# Analog_Power.net
KiCad netlist of a schematic drawn in Altium Designer
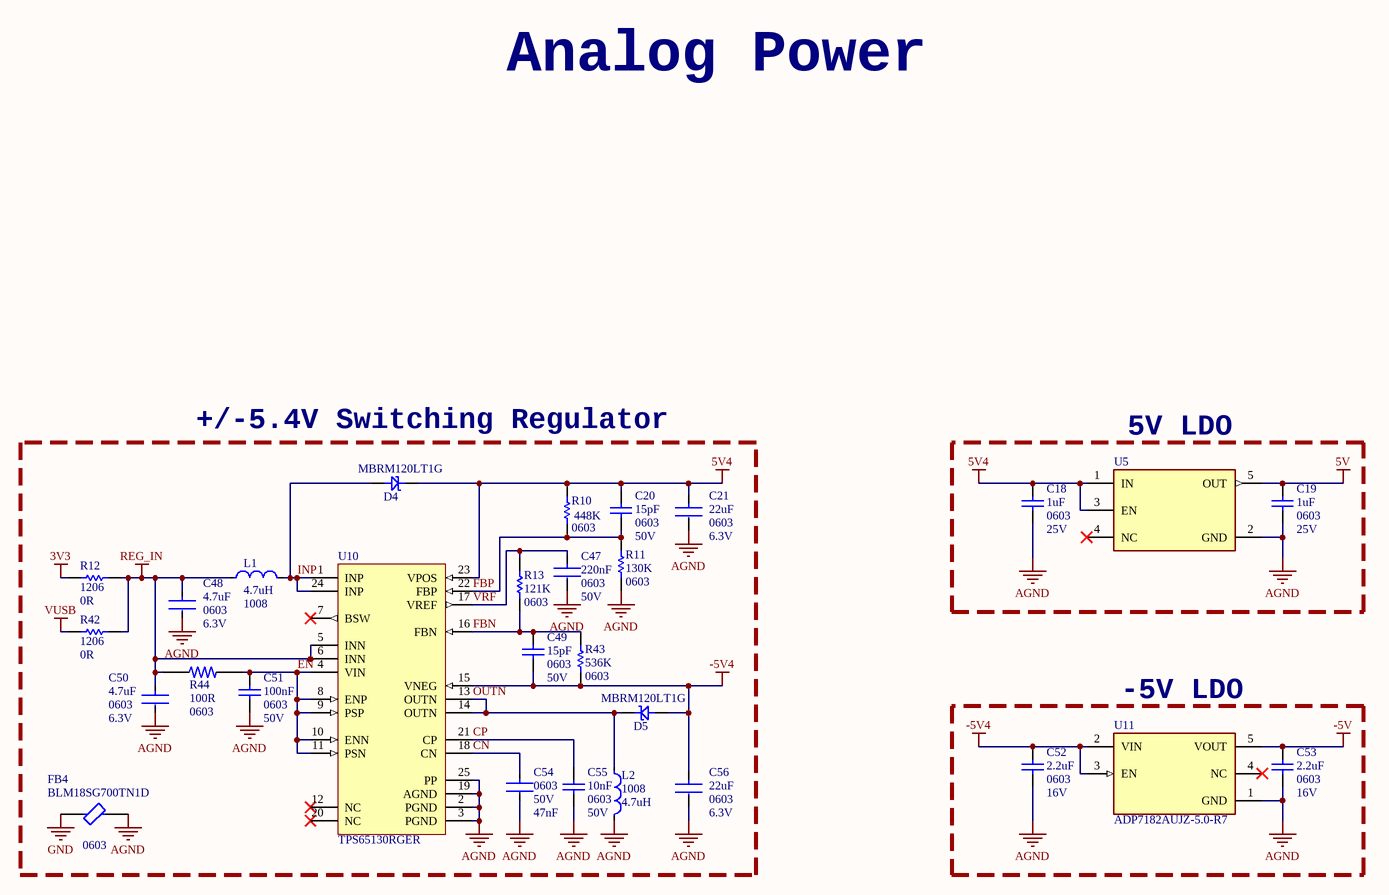
[diagram p0: Analog_Power.SchDoc]

(export (version "E")
  (design (tool "Eeschema 10.0.6"))
  (components
    (comp (ref "C18")
      (value "1uF")
      (footprint "C0603-V2")
      (description "CAP CER 1UF 25V X5R 0603")
      (fields
        (field (name "MANUFACTURER") "Samsung")
        (field (name "MANUFACTURER PART NUMBER") "CL10A105KA8NNNC")
        (field (name "CASE/PACKAGE") "0603")
        (field (name "RATED DC VOLTAGE (URDC)") "25V")
      )
      (libsource (lib "ETS_Library") (part "CL10A105KA8NNNC"))
    )
    (comp (ref "C19")
      (value "1uF")
      (footprint "C0603-V2")
      (description "CAP CER 1UF 25V X5R 0603")
      (fields
        (field (name "MANUFACTURER") "Samsung")
        (field (name "MANUFACTURER PART NUMBER") "CL10A105KA8NNNC")
        (field (name "CASE/PACKAGE") "0603")
        (field (name "RATED DC VOLTAGE (URDC)") "25V")
      )
      (libsource (lib "ETS_Library") (part "CL10A105KA8NNNC"))
    )
    (comp (ref "C20")
      (value "15pF")
      (footprint "C0603-V2")
      (description "CAP CER 15PF 50V C0G/NP0 0603")
      (fields
        (field (name "PACKAGING") "0603")
        (field (name "VOLTAGE") "50V")
        (field (name "Comment") "CL10C150JB8NNNC")
      )
      (libsource (lib "ETS_Library") (part "CL10C150JB8NNNC"))
    )
    (comp (ref "C21")
      (value "22uF")
      (footprint "BMS:C0603-V2")
      (description "CAP CER 22UF 6.3V X5R 0603")
      (fields
        (field (name "MANUFACTURER") "Murata")
        (field (name "MANUFACTURER PART NUMBER") "GRM188R60J226MEA0D")
        (field (name "RATED DC VOLTAGE (URDC)") "6.3V")
        (field (name "CASE/PACKAGE") "0603")
      )
      (libsource (lib "BMS") (part "GRM188R60J226MEA0D"))
    )
    (comp (ref "C47")
      (value "220nF")
      (footprint "C0603-V2")
      (description "CAP CER 0.22UF 50V X7R 0603")
      (fields
        (field (name "MANUFACTURER") "Murata")
        (field (name "MANUFACTURER PART NUMBER") "GRM188R71H224KAC4D")
        (field (name "VOLTAGE RATING") "50V")
        (field (name "CASE CODE (IMPERIAL)") "0603")
      )
      (libsource (lib "BMS") (part "GRM188R71H224KAC4D"))
    )
    (comp (ref "C48")
      (value "C0603C475K9PACTU")
      (footprint "FP-C0603-CG-IPC_B")
      (description "CAP CER 4.7UF 6.3V X5R 0603")
      (fields
        (field (name "PACKAGE") "0603")
        (field (name "TOLERANCE") "10%")
        (field (name "MANUFACTURER") "Kemet")
        (field (name "CAPACITANCE") "4.7uF")
        (field (name "VOLTAGE RATING") "6.3V")
      )
      (libsource (lib "ETS_Library") (part "CMP-2006-02256-2"))
    )
    (comp (ref "C49")
      (value "15pF")
      (footprint "C0603-V2")
      (description "CAP CER 15PF 50V C0G/NP0 0603")
      (fields
        (field (name "PACKAGING") "0603")
        (field (name "VOLTAGE") "50V")
        (field (name "Comment") "CL10C150JB8NNNC")
      )
      (libsource (lib "ETS_Library") (part "CL10C150JB8NNNC"))
    )
    (comp (ref "C50")
      (value "C0603C475K9PACTU")
      (footprint "FP-C0603-CG-IPC_B")
      (description "CAP CER 4.7UF 6.3V X5R 0603")
      (fields
        (field (name "PACKAGE") "0603")
        (field (name "TOLERANCE") "10%")
        (field (name "MANUFACTURER") "Kemet")
        (field (name "CAPACITANCE") "4.7uF")
        (field (name "VOLTAGE RATING") "6.3V")
      )
      (libsource (lib "ETS_Library") (part "CMP-2006-02256-2"))
    )
    (comp (ref "C51")
      (value "100nF")
      (footprint "C0603-V2")
      (description "CAP CER 0.1UF 50V X7R 0603")
      (fields
        (field (name "MANUFACTURER") "Samsung")
        (field (name "MANUFACTURER PART NUMBER") "CL10B104KB8NNWC")
        (field (name "CASE/PACKAGE") "0603")
        (field (name "VOLTAGE RATING") "50V")
      )
      (libsource (lib "ETS_Library") (part "CL10B104KB8NNWC"))
    )
    (comp (ref "C52")
      (value "2.2uF")
      (footprint "C0603-V2")
      (description "CAP CER 2.2UF 16V X5R 0603")
      (fields
        (field (name "MANUFACTURER") "Samsung")
        (field (name "MANUFACTURER PART NUMBER") "CL10A225KO8NNNC")
        (field (name "CASE/PACKAGE") "0603")
        (field (name "RATED DC VOLTAGE (URDC)") "16V")
      )
      (libsource (lib "ETS_Library") (part "CL10A225KO8NNNC"))
    )
    (comp (ref "C53")
      (value "2.2uF")
      (footprint "C0603-V2")
      (description "CAP CER 2.2UF 16V X5R 0603")
      (fields
        (field (name "MANUFACTURER") "Samsung")
        (field (name "MANUFACTURER PART NUMBER") "CL10A225KO8NNNC")
        (field (name "CASE/PACKAGE") "0603")
        (field (name "RATED DC VOLTAGE (URDC)") "16V")
      )
      (libsource (lib "ETS_Library") (part "CL10A225KO8NNNC"))
    )
    (comp (ref "C54")
      (value "GCJ188R71H473KA12D")
      (footprint "C0603")
      (description "Cap Ceramic 47000pF 50V X7R 10% Pad SMD 0603 Soft Termination +125°C Automotive T/R")
      (fields
        (field (name "TOLERANCE") "10%")
        (field (name "CASE CODE (IMPERIAL)") "0603")
        (field (name "VOLTAGE RATING") "50V")
        (field (name "CAPACITANCE") "47nF")
      )
      (libsource (lib "ETS_Library") (part "CMP-2006-02231-3"))
    )
    (comp (ref "C55")
      (value "GRM188R71H103KA01D")
      (footprint "C0603-V2")
      (description "Chip Capacitor, 10 nF, +/- 10%, 50 V, -55 to 125 degC, 0603 (1608 Metric), RoHS, Tape and Reel")
      (fields
        (field (name "VOLTAGE RATING") "50V")
        (field (name "CASE/PACKAGE") "0603")
        (field (name "VOLTAGE") "50V")
        (field (name "TOLERANCE") "10%")
        (field (name "CAPACITANCE") "10nF")
      )
      (libsource (lib "ETS_Library") (part "CMP-2100-03642-1"))
    )
    (comp (ref "C56")
      (value "22uF")
      (footprint "BMS:C0603-V2")
      (description "CAP CER 22UF 6.3V X5R 0603")
      (fields
        (field (name "MANUFACTURER") "Murata")
        (field (name "MANUFACTURER PART NUMBER") "GRM188R60J226MEA0D")
        (field (name "RATED DC VOLTAGE (URDC)") "6.3V")
        (field (name "CASE/PACKAGE") "0603")
      )
      (libsource (lib "BMS") (part "GRM188R60J226MEA0D"))
    )
    (comp (ref "D4")
      (value "MBRM120LT1G")
      (footprint "ONSC-POWERMITE-2-457-04_D_V")
      (description "DIODE SCHOTTKY 20V 1A POWERMITE")
      (fields (field (name "MANUFACTURER") "On Semiconductor"))
      (libsource (lib "ETS_Library") (part "MBRM120LT1G"))
    )
    (comp (ref "D5")
      (value "MBRM120LT1G")
      (footprint "ONSC-POWERMITE-2-457-04_D_V")
      (description "DIODE SCHOTTKY 20V 1A POWERMITE")
      (fields (field (name "MANUFACTURER") "On Semiconductor"))
      (libsource (lib "ETS_Library") (part "MBRM120LT1G"))
    )
    (comp (ref "FB4")
      (value "BLM18SG700TN1D")
      (footprint "BMS:BLM18SG700TN1D-MFG")
      (description "FERRITE BEAD 70 OHM 0603 1LN")
      (fields
        (field (name "TOLERANCE") "25%")
        (field (name "MANUFACTURER") "Murata")
        (field (name "CASE CODE (IMPERIAL)") "0603")
      )
      (libsource (lib "BMS") (part "BLM18SG700TN1D"))
    )
    (comp (ref "L1")
      (value "1239AS-H-4R7M=P2")
      (footprint "FP-DFE252012C-MFG")
      (description "Shielded Wirewound Inductor 4.7uH 20% 1300mA 0.24Ω 1008 (2520)")
      (fields
        (field (name "CASE/PACKAGE") "1008")
        (field (name "INDUCTANCE") "4.7uH")
        (field (name "TOLERANCE") "20%")
      )
      (libsource (lib "ETS_Library") (part "1239AS-H-4R7M=P2"))
    )
    (comp (ref "L2")
      (value "1239AS-H-4R7M=P2")
      (footprint "FP-DFE252012C-MFG")
      (description "Shielded Wirewound Inductor 4.7uH 20% 1300mA 0.24Ω 1008 (2520)")
      (fields
        (field (name "CASE/PACKAGE") "1008")
        (field (name "INDUCTANCE") "4.7uH")
        (field (name "TOLERANCE") "20%")
      )
      (libsource (lib "ETS_Library") (part "1239AS-H-4R7M=P2"))
    )
    (comp (ref "R10")
      (value "448K")
      (footprint "R0603")
      (description "RES 448K OHM 0.1% 1/10W 0603")
      (fields (field (name "CASE/PACKAGE") "0603") (field (name "Comment") "RT0603BRD07448KL"))
      (libsource (lib "ETS_Library") (part "RT0603BRD07448KL"))
    )
    (comp (ref "R11")
      (value "130K")
      (footprint "R0603")
      (description "RES SMD 130K OHM 1% 1/10W 0603")
      (fields (field (name "CASE/PACKAGE") "0603") (field (name "Comment") "AC0603FR-07130KL"))
      (libsource (lib "ETS_Library") (part "AC0603FR-07130KL"))
    )
    (comp (ref "R12")
      (value "RC1206JR-070RL")
      (footprint "BMS:R1206")
      (description "RES 0 OHM JUMPER 1/4W 1206")
      (fields
        (field (name "MANUFACTURER") "YAGEO")
        (field (name "OCTOPART") "https://octopart.com/rc1206jr-070rl-yageo-40025601")
        (field (name "CASE/PACKAGE") "1206")
        (field (name "RESISTANCE") "0R")
      )
      (libsource (lib "BMS") (part "RC1206JR-070RL"))
    )
    (comp (ref "R13")
      (value "121K")
      (footprint "R0603")
      (description "RES 121K OHM 1% 1/10W 0603")
      (fields (field (name "CASE/PACKAGE") "0603") (field (name "Comment") "RC0603FR-07121KL"))
      (libsource (lib "ETS_Library") (part "RC0603FR-07121KL"))
    )
    (comp (ref "R42")
      (value "RC1206JR-070RL")
      (footprint "BMS:R1206")
      (description "RES 0 OHM JUMPER 1/4W 1206")
      (fields
        (field (name "MANUFACTURER") "YAGEO")
        (field (name "OCTOPART") "https://octopart.com/rc1206jr-070rl-yageo-40025601")
        (field (name "CASE/PACKAGE") "1206")
        (field (name "RESISTANCE") "0R")
      )
      (libsource (lib "BMS") (part "RC1206JR-070RL"))
    )
    (comp (ref "R43")
      (value "536K")
      (footprint "R0603")
      (description "RES 536K OHM 1% 1/10W 0603")
      (fields (field (name "CASE/PACKAGE") "0603") (field (name "Comment") "RC0603FR-07536KL"))
      (libsource (lib "ETS_Library") (part "RC0603FR-07536KL"))
    )
    (comp (ref "R44")
      (value "100R")
      (footprint "R0603")
      (description "RES 100 OHM 1% 1/10W 0603")
      (fields
        (field (name "MP") "RC0603FR-07100RL")
        (field (name "MANUFACTURER") "Yageo Group")
        (field (name "CASE/PACKAGE") "0603")
      )
      (libsource (lib "ETS_Library") (part "RC0603FR-07100RL"))
    )
    (comp (ref "U5")
      (value "NCP161ASN500T1G")
      (footprint "FP-527AH-MFG")
      (description "IC REG LINEAR 5V 450MA SOT23-5")
      (fields (field (name "MANUFACTURER") "onsemi"))
      (libsource (lib "BMS") (part "NCP161ASN500T1G"))
    )
    (comp (ref "U10")
      (value "TPS65130RGER")
      (footprint "TI-RGE24-2450X2450TP_V")
      (fields (field (name "MANUFACTURER") "Texas Instruments"))
      (libsource (lib "ETS_Library") (part "CMP-0388-00548-1"))
    )
    (comp (ref "U11")
      (value "ADP7182AUJZ-5.0-R7")
      (footprint "FP-UJ-5-IPC_B")
      (description "IC REG LIN -5V 200MA TSOT-23-5")
      (fields (field (name "MANUFACTURER") "Analog Devices"))
      (libsource (lib "BMS") (part "ADP7182AUJZ-5.0-R7"))
    )
  )
  (nets
    (net (code "1") (name "-5V") (class "Default")
      (node (ref "C53") (pin "2") (pinfunction "2_2") (pintype "passive"))
      (node (ref "U11") (pin "5") (pinfunction "VOUT_5") (pintype "power_in"))
    )
    (net (code "2") (name "-5V4") (class "Default")
      (node (ref "C49") (pin "1") (pinfunction "1_1") (pintype "passive"))
      (node (ref "C52") (pin "2") (pinfunction "2_2") (pintype "passive"))
      (node (ref "C56") (pin "1") (pinfunction "1_1") (pintype "passive"))
      (node (ref "D5") (pin "2") (pinfunction "A_2") (pintype "passive"))
      (node (ref "R43") (pin "2") (pinfunction "2_2") (pintype "passive"))
      (node (ref "U10") (pin "15") (pinfunction "VNEG_15") (pintype "input"))
      (node (ref "U11") (pin "2") (pinfunction "VIN_2") (pintype "power_in"))
      (node (ref "U11") (pin "3") (pinfunction "EN_3") (pintype "input"))
    )
    (net (code "4") (name "/CN") (class "Default")
      (node (ref "C54") (pin "2") (pinfunction "2_2") (pintype "passive"))
      (node (ref "U10") (pin "18") (pinfunction "CN_18") (pintype "passive"))
    )
    (net (code "5") (name "/CP") (class "Default")
      (node (ref "C55") (pin "2") (pinfunction "2_2") (pintype "passive"))
      (node (ref "U10") (pin "21") (pinfunction "CP_21") (pintype "passive"))
    )
    (net (code "6") (name "/EN") (class "Default")
      (node (ref "C51") (pin "1") (pinfunction "1_1") (pintype "passive"))
      (node (ref "R44") (pin "2") (pinfunction "2_2") (pintype "passive"))
      (node (ref "U10") (pin "10") (pinfunction "ENN_10") (pintype "input"))
      (node (ref "U10") (pin "11") (pinfunction "PSN_11") (pintype "input"))
      (node (ref "U10") (pin "4") (pinfunction "VIN_4") (pintype "power_in"))
      (node (ref "U10") (pin "8") (pinfunction "ENP_8") (pintype "input"))
      (node (ref "U10") (pin "9") (pinfunction "PSP_9") (pintype "input"))
    )
    (net (code "7") (name "/FBN") (class "Default")
      (node (ref "C49") (pin "2") (pinfunction "2_2") (pintype "passive"))
      (node (ref "R13") (pin "2") (pinfunction "2_2") (pintype "passive"))
      (node (ref "R43") (pin "1") (pinfunction "1_1") (pintype "passive"))
      (node (ref "U10") (pin "16") (pinfunction "FBN_16") (pintype "input"))
    )
    (net (code "8") (name "/FBP") (class "Default")
      (node (ref "C20") (pin "1") (pinfunction "1_1") (pintype "passive"))
      (node (ref "R10") (pin "2") (pinfunction "2_2") (pintype "passive"))
      (node (ref "R11") (pin "1") (pinfunction "1_1") (pintype "passive"))
      (node (ref "U10") (pin "22") (pinfunction "FBP_22") (pintype "input"))
    )
    (net (code "9") (name "/INP") (class "Default")
      (node (ref "D4") (pin "2") (pinfunction "A_2") (pintype "passive"))
      (node (ref "L1") (pin "2") (pinfunction "2_2") (pintype "passive"))
      (node (ref "U10") (pin "1") (pinfunction "INP_1") (pintype "power_in"))
      (node (ref "U10") (pin "24") (pinfunction "INP_24") (pintype "power_in"))
    )
    (net (code "10") (name "/OUTN") (class "Default")
      (node (ref "D5") (pin "1") (pinfunction "K_1") (pintype "passive"))
      (node (ref "L2") (pin "1") (pinfunction "1_1") (pintype "passive"))
      (node (ref "U10") (pin "13") (pinfunction "OUTN_13") (pintype "power_in"))
      (node (ref "U10") (pin "14") (pinfunction "OUTN_14") (pintype "power_in"))
    )
    (net (code "11") (name "/VRF") (class "Default")
      (node (ref "C47") (pin "1") (pinfunction "1_1") (pintype "passive"))
      (node (ref "R13") (pin "1") (pinfunction "1_1") (pintype "passive"))
      (node (ref "U10") (pin "17") (pinfunction "VREF_17") (pintype "output"))
    )
    (net (code "12") (name "3V3") (class "Default")
      (node (ref "R12") (pin "1") (pinfunction "1_1") (pintype "passive"))
    )
    (net (code "13") (name "5V") (class "Default")
      (node (ref "C19") (pin "2") (pinfunction "2_2") (pintype "passive"))
      (node (ref "U5") (pin "5") (pinfunction "OUT_5") (pintype "output"))
    )
    (net (code "14") (name "5V4") (class "Default")
      (node (ref "C18") (pin "2") (pinfunction "2_2") (pintype "passive"))
      (node (ref "C20") (pin "2") (pinfunction "2_2") (pintype "passive"))
      (node (ref "C21") (pin "1") (pinfunction "1_1") (pintype "passive"))
      (node (ref "D4") (pin "1") (pinfunction "K_1") (pintype "passive"))
      (node (ref "R10") (pin "1") (pinfunction "1_1") (pintype "passive"))
      (node (ref "U10") (pin "23") (pinfunction "VPOS_23") (pintype "input"))
      (node (ref "U5") (pin "1") (pinfunction "IN_1") (pintype "power_in"))
      (node (ref "U5") (pin "3") (pinfunction "EN_3") (pintype "passive"))
    )
    (net (code "15") (name "AGND") (class "Default")
      (node (ref "C18") (pin "1") (pinfunction "1_1") (pintype "passive"))
      (node (ref "C19") (pin "1") (pinfunction "1_1") (pintype "passive"))
      (node (ref "C21") (pin "2") (pinfunction "2_2") (pintype "passive"))
      (node (ref "C47") (pin "2") (pinfunction "2_2") (pintype "passive"))
      (node (ref "C48") (pin "2") (pinfunction "2_2") (pintype "passive"))
      (node (ref "C50") (pin "2") (pinfunction "2_2") (pintype "passive"))
      (node (ref "C51") (pin "2") (pinfunction "2_2") (pintype "passive"))
      (node (ref "C52") (pin "1") (pinfunction "1_1") (pintype "passive"))
      (node (ref "C53") (pin "1") (pinfunction "1_1") (pintype "passive"))
      (node (ref "C54") (pin "1") (pinfunction "1_1") (pintype "passive"))
      (node (ref "C55") (pin "1") (pinfunction "1_1") (pintype "passive"))
      (node (ref "C56") (pin "2") (pinfunction "2_2") (pintype "passive"))
      (node (ref "FB4") (pin "2") (pinfunction "2_2") (pintype "passive"))
      (node (ref "L2") (pin "2") (pinfunction "2_2") (pintype "passive"))
      (node (ref "R11") (pin "2") (pinfunction "2_2") (pintype "passive"))
      (node (ref "U10") (pin "19") (pinfunction "AGND_19") (pintype "power_in"))
      (node (ref "U10") (pin "2") (pinfunction "PGND_2") (pintype "power_in"))
      (node (ref "U10") (pin "25") (pinfunction "PP_25") (pintype "power_in"))
      (node (ref "U10") (pin "3") (pinfunction "PGND_3") (pintype "power_in"))
      (node (ref "U11") (pin "1") (pinfunction "GND_1") (pintype "power_in"))
      (node (ref "U5") (pin "2") (pinfunction "GND_2") (pintype "power_in"))
    )
    (net (code "16") (name "GND") (class "Default")
      (node (ref "FB4") (pin "1") (pinfunction "1_1") (pintype "passive"))
    )
    (net (code "17") (name "REG_IN") (class "Default")
      (node (ref "C48") (pin "1") (pinfunction "1_1") (pintype "passive"))
      (node (ref "C50") (pin "1") (pinfunction "1_1") (pintype "passive"))
      (node (ref "L1") (pin "1") (pinfunction "1_1") (pintype "passive"))
      (node (ref "R12") (pin "2") (pinfunction "2_2") (pintype "passive"))
      (node (ref "R42") (pin "2") (pinfunction "2_2") (pintype "passive"))
      (node (ref "R44") (pin "1") (pinfunction "1_1") (pintype "passive"))
      (node (ref "U10") (pin "5") (pinfunction "INN_5") (pintype "power_in"))
      (node (ref "U10") (pin "6") (pinfunction "INN_6") (pintype "power_in"))
    )
    (net (code "18") (name "VUSB") (class "Default")
      (node (ref "R42") (pin "1") (pinfunction "1_1") (pintype "passive"))
    )
    (net (code "19") (name "unconnected-(U5-NC-Pad4)") (class "Default")
      (node (ref "U5") (pin "4") (pinfunction "NC_4") (pintype "passive+no_connect"))
    )
    (net (code "20") (name "unconnected-(U10-BSW-Pad7)") (class "Default")
      (node (ref "U10") (pin "7") (pinfunction "BSW_7") (pintype "output+no_connect"))
    )
    (net (code "21") (name "unconnected-(U10-NC-Pad12)") (class "Default")
      (node (ref "U10") (pin "12") (pinfunction "NC_12") (pintype "passive+no_connect"))
    )
    (net (code "22") (name "unconnected-(U10-NC-Pad20)") (class "Default")
      (node (ref "U10") (pin "20") (pinfunction "NC_20") (pintype "passive+no_connect"))
    )
    (net (code "23") (name "unconnected-(U11-NC-Pad4)") (class "Default")
      (node (ref "U11") (pin "4") (pinfunction "NC_4") (pintype "passive+no_connect"))
    )
  )
)
